# 780-00012-P3_rev4_Sch_M2_Focus_Drive.net
KiCad netlist of a schematic drawn in Altium Designer
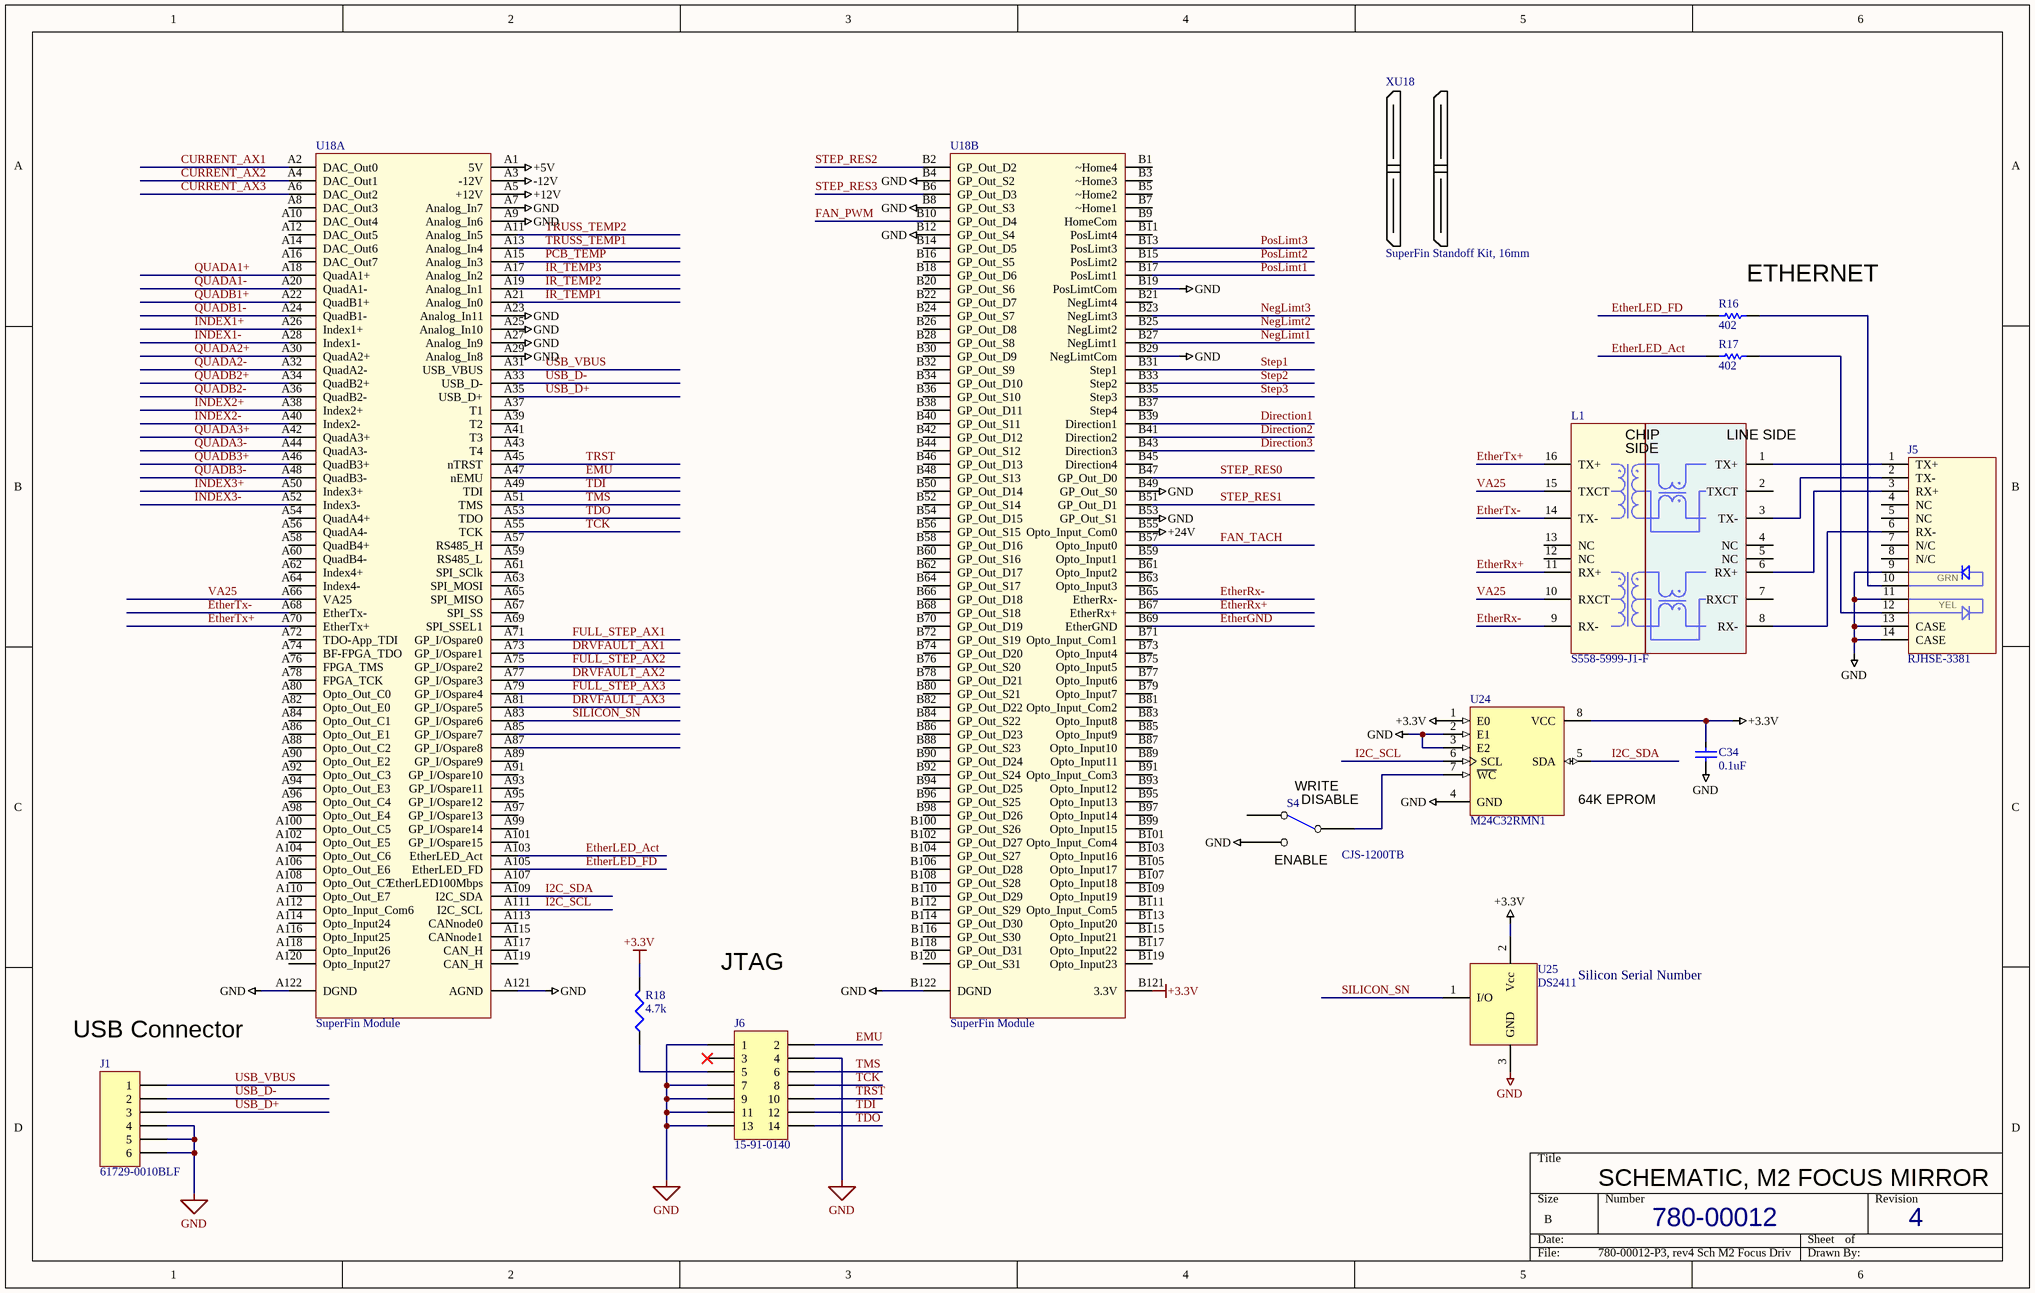
[diagram p0: 780-00012-P3, rev4 Sch M2 Focus Drive.SchDoc]

(export (version "E")
  (design (tool "Eeschema 10.0.6"))
  (components
    (comp (ref "C34")
      (value "0.1uF")
      (footprint "SMD_0805")
      (description "Capacitor")
      (fields (field (name "MANUFACTURER") "AVX") (field (name "Comment") "Cap SMD"))
      (libsource (lib "Richs Schematic Components") (part "Cap SMD"))
    )
    (comp (ref "J1")
      (value "61729-0010BLF")
      (footprint "USB Vertical PCB")
      (description "Header, 6-Pin")
      (fields (field (name "MANUFACTURER") "FCI"))
      (libsource (lib "Miscellaneous Connectors") (part "Header 6"))
    )
    (comp (ref "J5")
      (value "RJHSE-3381")
      (footprint "RJ45, VERT MOUNT, NO MAGNETICS")
      (description "Vertical PC mount, w/o magnetics")
      (libsource (lib "Richs Schematic Components") (part "CONN RJ-45 w/o magnetics"))
    )
    (comp (ref "J6")
      (value "15-91-0140")
      (footprint "HDR2X7")
      (description "Header, 7-Pin, Dual row")
      (fields (field (name "MANUFACTURER") "Molex/Waldom"))
      (libsource (lib "Miscellaneous Connectors") (part "Header 7X2"))
    )
    (comp (ref "L1")
      (value "S558-5999-J1-F")
      (footprint "10/100BT Magetics module")
      (description "10/100BT Magnetics Module")
      (libsource (lib "Richs Schematic Components") (part "Ethernet Magnetics module"))
    )
    (comp (ref "R16")
      (value "402")
      (footprint "SMD_0805")
      (description "Resistor 0805")
      (fields (field (name "MANUFACTURER") "Vishay/Dale") (field (name "Comment") "Res 0805"))
      (libsource (lib "Richs Schematic Components") (part "Res SMD"))
    )
    (comp (ref "R17")
      (value "402")
      (footprint "SMD_0805")
      (description "Resistor 0805")
      (fields (field (name "MANUFACTURER") "Vishay/Dale") (field (name "Comment") "Res 0805"))
      (libsource (lib "Richs Schematic Components") (part "Res SMD"))
    )
    (comp (ref "R18")
      (value "4.7k")
      (footprint "2012[0805]")
      (description "Resistor")
      (fields (field (name "MANUFACTURER") "Dale/Vishay"))
      (libsource (lib "Miscellaneous Devices") (part "Res3"))
    )
    (comp (ref "S4")
      (value "CJS-1200TB")
      (footprint "CAS-120B")
      (fields (field (name "MANUFACTURER") "Copal Electronics"))
      (libsource (lib "JON_1_Library") (part "SW_SPDT_DOUG"))
    )
    (comp (ref "U18")
      (value "SuperFin Module")
      (footprint "SuperFin Footprint")
      (libsource (lib "Richs Schematic Components") (part "SuperFin Module"))
    )
    (comp (ref "U24")
      (value "M24C32RMN1")
      (footprint "SOP8_N")
      (description "32 Kbit Serial I²C Bus EEPROM")
      (libsource (lib "ST Memory EEPROM Serial") (part "M24C32RMN1"))
    )
    (comp (ref "U25")
      (value "DS2411")
      (footprint "SMD_SOT23_3")
      (description "Silicon Serial Number")
      (fields (field (name "MANUFACTURER") "MAXIM"))
      (libsource (lib "Richs Schematic Components") (part "DS2411"))
    )
    (comp (ref "XU18")
      (value "SuperFin Standoff Kit, 16mm")
      (libsource (lib "Richs Schematic Components") (part "SuperFin Standoff Kit, 16mm"))
    )
  )
  (nets
    (net (code "1") (name "+3.3V") (class "Default")
      (node (ref "C34") (pin "2") (pinfunction "2_2") (pintype "passive"))
      (node (ref "R18") (pin "2") (pinfunction "2_2") (pintype "passive"))
      (node (ref "U18") (pin "B121") (pinfunction "3.3V_B121") (pintype "passive"))
      (node (ref "U24") (pin "1") (pinfunction "E0_1") (pintype "input"))
      (node (ref "U24") (pin "8") (pinfunction "VCC_8") (pintype "power_in"))
      (node (ref "U25") (pin "2") (pinfunction "Vcc_2") (pintype "passive"))
    )
    (net (code "2") (name "+5V") (class "Default")
      (node (ref "U18") (pin "A1") (pinfunction "5V_A1") (pintype "passive"))
    )
    (net (code "3") (name "+12V") (class "Default")
      (node (ref "U18") (pin "A5") (pinfunction "+12V_A5") (pintype "passive"))
    )
    (net (code "4") (name "+24V") (class "Default")
      (node (ref "U18") (pin "B55") (pinfunction "Opto_Input_Com0_B55") (pintype "passive"))
    )
    (net (code "5") (name "-12V") (class "Default")
      (node (ref "U18") (pin "A3") (pinfunction "-12V_A3") (pintype "passive"))
    )
    (net (code "6") (name "/CURRENT_AX1") (class "Default")
      (node (ref "U18") (pin "A2") (pinfunction "DAC_Out0_A2") (pintype "passive"))
    )
    (net (code "7") (name "/CURRENT_AX2") (class "Default")
      (node (ref "U18") (pin "A4") (pinfunction "DAC_Out1_A4") (pintype "passive"))
    )
    (net (code "8") (name "/CURRENT_AX3") (class "Default")
      (node (ref "U18") (pin "A6") (pinfunction "DAC_Out2_A6") (pintype "passive"))
    )
    (net (code "9") (name "/DRVFAULT_AX1") (class "Default")
      (node (ref "U18") (pin "A73") (pinfunction "GP_I/Ospare1_A73") (pintype "passive"))
    )
    (net (code "10") (name "/DRVFAULT_AX2") (class "Default")
      (node (ref "U18") (pin "A77") (pinfunction "GP_I/Ospare3_A77") (pintype "passive"))
    )
    (net (code "11") (name "/DRVFAULT_AX3") (class "Default")
      (node (ref "U18") (pin "A81") (pinfunction "GP_I/Ospare5_A81") (pintype "passive"))
    )
    (net (code "12") (name "/Direction1") (class "Default")
      (node (ref "U18") (pin "B39") (pinfunction "Direction1_B39") (pintype "passive"))
    )
    (net (code "13") (name "/Direction2") (class "Default")
      (node (ref "U18") (pin "B41") (pinfunction "Direction2_B41") (pintype "passive"))
    )
    (net (code "14") (name "/Direction3") (class "Default")
      (node (ref "U18") (pin "B43") (pinfunction "Direction3_B43") (pintype "passive"))
    )
    (net (code "15") (name "/EMU") (class "Default")
      (node (ref "J6") (pin "2") (pinfunction "2_2") (pintype "passive"))
      (node (ref "U18") (pin "A47") (pinfunction "nEMU_A47") (pintype "passive"))
    )
    (net (code "16") (name "/EtherGND") (class "Default")
      (node (ref "U18") (pin "B69") (pinfunction "EtherGND_B69") (pintype "passive"))
    )
    (net (code "17") (name "/EtherLED_Act") (class "Default")
      (node (ref "R17") (pin "1") (pinfunction "1_1") (pintype "passive"))
      (node (ref "U18") (pin "A103") (pinfunction "EtherLED_Act_A103") (pintype "passive"))
    )
    (net (code "18") (name "/EtherLED_FD") (class "Default")
      (node (ref "R16") (pin "1") (pinfunction "1_1") (pintype "passive"))
      (node (ref "U18") (pin "A105") (pinfunction "EtherLED_FD_A105") (pintype "passive"))
    )
    (net (code "19") (name "/EtherRx+") (class "Default")
      (node (ref "L1") (pin "11") (pinfunction "RX+_11") (pintype "passive"))
      (node (ref "U18") (pin "B67") (pinfunction "EtherRx+_B67") (pintype "passive"))
    )
    (net (code "20") (name "/EtherRx-") (class "Default")
      (node (ref "L1") (pin "9") (pinfunction "RX-_9") (pintype "passive"))
      (node (ref "U18") (pin "B65") (pinfunction "EtherRx-_B65") (pintype "passive"))
    )
    (net (code "21") (name "/EtherTx+") (class "Default")
      (node (ref "L1") (pin "16") (pinfunction "TX+_16") (pintype "passive"))
      (node (ref "U18") (pin "A70") (pinfunction "EtherTx+_A70") (pintype "passive"))
    )
    (net (code "22") (name "/EtherTx-") (class "Default")
      (node (ref "L1") (pin "14") (pinfunction "TX-_14") (pintype "passive"))
      (node (ref "U18") (pin "A68") (pinfunction "EtherTx-_A68") (pintype "passive"))
    )
    (net (code "23") (name "/FAN_PWM") (class "Default")
      (node (ref "U18") (pin "B10") (pinfunction "GP_Out_D4_B10") (pintype "passive"))
    )
    (net (code "24") (name "/FAN_TACH") (class "Default")
      (node (ref "U18") (pin "B57") (pinfunction "Opto_Input0_B57") (pintype "passive"))
    )
    (net (code "25") (name "/FULL_STEP_AX1") (class "Default")
      (node (ref "U18") (pin "A71") (pinfunction "GP_I/Ospare0_A71") (pintype "passive"))
    )
    (net (code "26") (name "/FULL_STEP_AX2") (class "Default")
      (node (ref "U18") (pin "A75") (pinfunction "GP_I/Ospare2_A75") (pintype "passive"))
    )
    (net (code "27") (name "/FULL_STEP_AX3") (class "Default")
      (node (ref "U18") (pin "A79") (pinfunction "GP_I/Ospare4_A79") (pintype "passive"))
    )
    (net (code "28") (name "/I2C_SCL") (class "Default")
      (node (ref "U18") (pin "A111") (pinfunction "I2C_SCL_A111") (pintype "passive"))
      (node (ref "U24") (pin "6") (pinfunction "SCL_6") (pintype "input"))
    )
    (net (code "29") (name "/I2C_SDA") (class "Default")
      (node (ref "U18") (pin "A109") (pinfunction "I2C_SDA_A109") (pintype "passive"))
      (node (ref "U24") (pin "5") (pinfunction "SDA_5") (pintype "bidirectional"))
    )
    (net (code "30") (name "/INDEX1+") (class "Default")
      (node (ref "U18") (pin "A26") (pinfunction "Index1+_A26") (pintype "passive"))
    )
    (net (code "31") (name "/INDEX1-") (class "Default")
      (node (ref "U18") (pin "A28") (pinfunction "Index1-_A28") (pintype "passive"))
    )
    (net (code "32") (name "/INDEX2+") (class "Default")
      (node (ref "U18") (pin "A38") (pinfunction "Index2+_A38") (pintype "passive"))
    )
    (net (code "33") (name "/INDEX2-") (class "Default")
      (node (ref "U18") (pin "A40") (pinfunction "Index2-_A40") (pintype "passive"))
    )
    (net (code "34") (name "/INDEX3+") (class "Default")
      (node (ref "U18") (pin "A50") (pinfunction "Index3+_A50") (pintype "passive"))
    )
    (net (code "35") (name "/INDEX3-") (class "Default")
      (node (ref "U18") (pin "A52") (pinfunction "Index3-_A52") (pintype "passive"))
    )
    (net (code "36") (name "/IR_TEMP1") (class "Default")
      (node (ref "U18") (pin "A21") (pinfunction "Analog_In0_A21") (pintype "passive"))
    )
    (net (code "37") (name "/IR_TEMP2") (class "Default")
      (node (ref "U18") (pin "A19") (pinfunction "Analog_In1_A19") (pintype "passive"))
    )
    (net (code "38") (name "/IR_TEMP3") (class "Default")
      (node (ref "U18") (pin "A17") (pinfunction "Analog_In2_A17") (pintype "passive"))
    )
    (net (code "39") (name "/NegLimt1") (class "Default")
      (node (ref "U18") (pin "B27") (pinfunction "NegLimt1_B27") (pintype "passive"))
    )
    (net (code "40") (name "/NegLimt2") (class "Default")
      (node (ref "U18") (pin "B25") (pinfunction "NegLimt2_B25") (pintype "passive"))
    )
    (net (code "41") (name "/NegLimt3") (class "Default")
      (node (ref "U18") (pin "B23") (pinfunction "NegLimt3_B23") (pintype "passive"))
    )
    (net (code "42") (name "/PCB_TEMP") (class "Default")
      (node (ref "U18") (pin "A15") (pinfunction "Analog_In3_A15") (pintype "passive"))
    )
    (net (code "43") (name "/PosLimt1") (class "Default")
      (node (ref "U18") (pin "B17") (pinfunction "PosLimt1_B17") (pintype "passive"))
    )
    (net (code "44") (name "/PosLimt2") (class "Default")
      (node (ref "U18") (pin "B15") (pinfunction "PosLimt2_B15") (pintype "passive"))
    )
    (net (code "45") (name "/PosLimt3") (class "Default")
      (node (ref "U18") (pin "B13") (pinfunction "PosLimt3_B13") (pintype "passive"))
    )
    (net (code "46") (name "/QUADA1+") (class "Default")
      (node (ref "U18") (pin "A18") (pinfunction "QuadA1+_A18") (pintype "passive"))
    )
    (net (code "47") (name "/QUADA1-") (class "Default")
      (node (ref "U18") (pin "A20") (pinfunction "QuadA1-_A20") (pintype "passive"))
    )
    (net (code "48") (name "/QUADA2+") (class "Default")
      (node (ref "U18") (pin "A30") (pinfunction "QuadA2+_A30") (pintype "passive"))
    )
    (net (code "49") (name "/QUADA2-") (class "Default")
      (node (ref "U18") (pin "A32") (pinfunction "QuadA2-_A32") (pintype "passive"))
    )
    (net (code "50") (name "/QUADA3+") (class "Default")
      (node (ref "U18") (pin "A42") (pinfunction "QuadA3+_A42") (pintype "passive"))
    )
    (net (code "51") (name "/QUADA3-") (class "Default")
      (node (ref "U18") (pin "A44") (pinfunction "QuadA3-_A44") (pintype "passive"))
    )
    (net (code "52") (name "/QUADB1+") (class "Default")
      (node (ref "U18") (pin "A22") (pinfunction "QuadB1+_A22") (pintype "passive"))
    )
    (net (code "53") (name "/QUADB1-") (class "Default")
      (node (ref "U18") (pin "A24") (pinfunction "QuadB1-_A24") (pintype "passive"))
    )
    (net (code "54") (name "/QUADB2+") (class "Default")
      (node (ref "U18") (pin "A34") (pinfunction "QuadB2+_A34") (pintype "passive"))
    )
    (net (code "55") (name "/QUADB2-") (class "Default")
      (node (ref "U18") (pin "A36") (pinfunction "QuadB2-_A36") (pintype "passive"))
    )
    (net (code "56") (name "/QUADB3+") (class "Default")
      (node (ref "U18") (pin "A46") (pinfunction "QuadB3+_A46") (pintype "passive"))
    )
    (net (code "57") (name "/QUADB3-") (class "Default")
      (node (ref "U18") (pin "A48") (pinfunction "QuadB3-_A48") (pintype "passive"))
    )
    (net (code "58") (name "/SILICON_SN") (class "Default")
      (node (ref "U18") (pin "A83") (pinfunction "GP_I/Ospare6_A83") (pintype "passive"))
      (node (ref "U25") (pin "1") (pinfunction "I/O_1") (pintype "passive"))
    )
    (net (code "59") (name "/STEP_RES0") (class "Default")
      (node (ref "U18") (pin "B47") (pinfunction "GP_Out_D0_B47") (pintype "passive"))
    )
    (net (code "60") (name "/STEP_RES1") (class "Default")
      (node (ref "U18") (pin "B51") (pinfunction "GP_Out_D1_B51") (pintype "passive"))
    )
    (net (code "61") (name "/STEP_RES2") (class "Default")
      (node (ref "U18") (pin "B2") (pinfunction "GP_Out_D2_B2") (pintype "passive"))
    )
    (net (code "62") (name "/STEP_RES3") (class "Default")
      (node (ref "U18") (pin "B6") (pinfunction "GP_Out_D3_B6") (pintype "passive"))
    )
    (net (code "63") (name "/Step1") (class "Default")
      (node (ref "U18") (pin "B31") (pinfunction "Step1_B31") (pintype "passive"))
    )
    (net (code "64") (name "/Step2") (class "Default")
      (node (ref "U18") (pin "B33") (pinfunction "Step2_B33") (pintype "passive"))
    )
    (net (code "65") (name "/Step3") (class "Default")
      (node (ref "U18") (pin "B35") (pinfunction "Step3_B35") (pintype "passive"))
    )
    (net (code "66") (name "/TCK") (class "Default")
      (node (ref "J6") (pin "8") (pinfunction "8_8") (pintype "passive"))
      (node (ref "U18") (pin "A55") (pinfunction "TCK_A55") (pintype "passive"))
    )
    (net (code "67") (name "/TDI") (class "Default")
      (node (ref "J6") (pin "12") (pinfunction "12_12") (pintype "passive"))
      (node (ref "U18") (pin "A49") (pinfunction "TDI_A49") (pintype "passive"))
    )
    (net (code "68") (name "/TDO") (class "Default")
      (node (ref "J6") (pin "14") (pinfunction "14_14") (pintype "passive"))
      (node (ref "U18") (pin "A53") (pinfunction "TDO_A53") (pintype "passive"))
    )
    (net (code "69") (name "/TMS") (class "Default")
      (node (ref "J6") (pin "6") (pinfunction "6_6") (pintype "passive"))
      (node (ref "U18") (pin "A51") (pinfunction "TMS_A51") (pintype "passive"))
    )
    (net (code "70") (name "/TRST") (class "Default")
      (node (ref "J6") (pin "10") (pinfunction "10_10") (pintype "passive"))
      (node (ref "U18") (pin "A45") (pinfunction "nTRST_A45") (pintype "passive"))
    )
    (net (code "71") (name "/TRUSS_TEMP1") (class "Default")
      (node (ref "U18") (pin "A13") (pinfunction "Analog_In4_A13") (pintype "passive"))
    )
    (net (code "72") (name "/TRUSS_TEMP2") (class "Default")
      (node (ref "U18") (pin "A11") (pinfunction "Analog_In5_A11") (pintype "passive"))
    )
    (net (code "73") (name "/USB_D+") (class "Default")
      (node (ref "J1") (pin "3") (pinfunction "3_3") (pintype "passive"))
      (node (ref "U18") (pin "A35") (pinfunction "USB_D+_A35") (pintype "passive"))
    )
    (net (code "74") (name "/USB_D-") (class "Default")
      (node (ref "J1") (pin "2") (pinfunction "2_2") (pintype "passive"))
      (node (ref "U18") (pin "A33") (pinfunction "USB_D-_A33") (pintype "passive"))
    )
    (net (code "75") (name "/USB_VBUS") (class "Default")
      (node (ref "J1") (pin "1") (pinfunction "1_1") (pintype "passive"))
      (node (ref "U18") (pin "A31") (pinfunction "USB_VBUS_A31") (pintype "passive"))
    )
    (net (code "76") (name "/VA25") (class "Default")
      (node (ref "L1") (pin "10") (pinfunction "RXCT_10") (pintype "passive"))
      (node (ref "L1") (pin "15") (pinfunction "TXCT_15") (pintype "passive"))
      (node (ref "U18") (pin "A66") (pinfunction "VA25_A66") (pintype "passive"))
    )
    (net (code "77") (name "GND") (class "Default")
      (node (ref "C34") (pin "1") (pinfunction "1_1") (pintype "passive"))
      (node (ref "J1") (pin "4") (pinfunction "4_4") (pintype "passive"))
      (node (ref "J1") (pin "5") (pinfunction "5_5") (pintype "passive"))
      (node (ref "J1") (pin "6") (pinfunction "6_6") (pintype "passive"))
      (node (ref "J5") (pin "11") (pinfunction "YEL-Cathode_11") (pintype "passive"))
      (node (ref "J5") (pin "13") (pinfunction "CASE_13") (pintype "passive"))
      (node (ref "J5") (pin "14") (pinfunction "CASE_14") (pintype "passive"))
      (node (ref "J5") (pin "9") (pinfunction "GRN-Anode_9") (pintype "passive"))
      (node (ref "J6") (pin "1") (pinfunction "1_1") (pintype "passive"))
      (node (ref "J6") (pin "11") (pinfunction "11_11") (pintype "passive"))
      (node (ref "J6") (pin "13") (pinfunction "13_13") (pintype "passive"))
      (node (ref "J6") (pin "4") (pinfunction "4_4") (pintype "passive"))
      (node (ref "J6") (pin "7") (pinfunction "7_7") (pintype "passive"))
      (node (ref "J6") (pin "9") (pinfunction "9_9") (pintype "passive"))
      (node (ref "S4") (pin "1") (pinfunction "NO_1") (pintype "passive"))
      (node (ref "U18") (pin "A121") (pinfunction "AGND_A121") (pintype "passive"))
      (node (ref "U18") (pin "A122") (pinfunction "DGND_A122") (pintype "passive"))
      (node (ref "U18") (pin "A23") (pinfunction "Analog_In11_A23") (pintype "passive"))
      (node (ref "U18") (pin "A25") (pinfunction "Analog_In10_A25") (pintype "passive"))
      (node (ref "U18") (pin "A27") (pinfunction "Analog_In9_A27") (pintype "passive"))
      (node (ref "U18") (pin "A29") (pinfunction "Analog_In8_A29") (pintype "passive"))
      (node (ref "U18") (pin "A7") (pinfunction "Analog_In7_A7") (pintype "passive"))
      (node (ref "U18") (pin "A9") (pinfunction "Analog_In6_A9") (pintype "passive"))
      (node (ref "U18") (pin "B12") (pinfunction "GP_Out_S4_B12") (pintype "passive"))
      (node (ref "U18") (pin "B122") (pinfunction "DGND_B122") (pintype "passive"))
      (node (ref "U18") (pin "B19") (pinfunction "PosLimtCom_B19") (pintype "passive"))
      (node (ref "U18") (pin "B29") (pinfunction "NegLimtCom_B29") (pintype "passive"))
      (node (ref "U18") (pin "B4") (pinfunction "GP_Out_S2_B4") (pintype "passive"))
      (node (ref "U18") (pin "B49") (pinfunction "GP_Out_S0_B49") (pintype "passive"))
      (node (ref "U18") (pin "B53") (pinfunction "GP_Out_S1_B53") (pintype "passive"))
      (node (ref "U18") (pin "B8") (pinfunction "GP_Out_S3_B8") (pintype "passive"))
      (node (ref "U24") (pin "2") (pinfunction "E1_2") (pintype "input"))
      (node (ref "U24") (pin "3") (pinfunction "E2_3") (pintype "input"))
      (node (ref "U24") (pin "4") (pinfunction "GND_4") (pintype "power_in"))
      (node (ref "U25") (pin "3") (pinfunction "GND_3") (pintype "passive"))
    )
    (net (code "78") (name "Net-(J5-GRN-Cathode)") (class "Default")
      (node (ref "J5") (pin "10") (pinfunction "GRN-Cathode_10") (pintype "passive"))
      (node (ref "R16") (pin "2") (pinfunction "2_2") (pintype "passive"))
    )
    (net (code "79") (name "Net-(J5-RX+)") (class "Default")
      (node (ref "J5") (pin "3") (pinfunction "RX+_3") (pintype "passive"))
      (node (ref "L1") (pin "6") (pinfunction "RX+_6") (pintype "passive"))
    )
    (net (code "80") (name "Net-(J5-RX-)") (class "Default")
      (node (ref "J5") (pin "6") (pinfunction "RX-_6") (pintype "passive"))
      (node (ref "L1") (pin "8") (pinfunction "RX-_8") (pintype "passive"))
    )
    (net (code "81") (name "Net-(J5-TX+)") (class "Default")
      (node (ref "J5") (pin "1") (pinfunction "TX+_1") (pintype "passive"))
      (node (ref "L1") (pin "1") (pinfunction "TX+_1") (pintype "passive"))
    )
    (net (code "82") (name "Net-(J5-TX-)") (class "Default")
      (node (ref "J5") (pin "2") (pinfunction "TX-_2") (pintype "passive"))
      (node (ref "L1") (pin "3") (pinfunction "TX-_3") (pintype "passive"))
    )
    (net (code "83") (name "Net-(J5-YEL-Anode)") (class "Default")
      (node (ref "J5") (pin "12") (pinfunction "YEL-Anode_12") (pintype "passive"))
      (node (ref "R17") (pin "2") (pinfunction "2_2") (pintype "passive"))
    )
    (net (code "84") (name "Net-(J6-Pad5)") (class "Default")
      (node (ref "J6") (pin "5") (pinfunction "5_5") (pintype "passive"))
      (node (ref "R18") (pin "1") (pinfunction "1_1") (pintype "passive"))
    )
    (net (code "85") (name "Net-(S4-COM)") (class "Default")
      (node (ref "S4") (pin "2") (pinfunction "COM_2") (pintype "passive"))
      (node (ref "U24") (pin "7") (pinfunction "~{WC}_7") (pintype "input"))
    )
    (net (code "86") (name "unconnected-(J5-NC-Pad4)") (class "Default")
      (node (ref "J5") (pin "4") (pinfunction "NC_4") (pintype "passive"))
    )
    (net (code "87") (name "unconnected-(J5-NC-Pad5)") (class "Default")
      (node (ref "J5") (pin "5") (pinfunction "NC_5") (pintype "passive"))
    )
    (net (code "88") (name "unconnected-(J5-N{slash}C-Pad7)") (class "Default")
      (node (ref "J5") (pin "7") (pinfunction "N/C_7") (pintype "passive"))
    )
    (net (code "89") (name "unconnected-(J5-N{slash}C-Pad8)") (class "Default")
      (node (ref "J5") (pin "8") (pinfunction "N/C_8") (pintype "passive"))
    )
    (net (code "90") (name "unconnected-(J6-Pad3)") (class "Default")
      (node (ref "J6") (pin "3") (pinfunction "3_3") (pintype "passive+no_connect"))
    )
    (net (code "91") (name "unconnected-(L1-NC-Pad4)") (class "Default")
      (node (ref "L1") (pin "4") (pinfunction "NC_4") (pintype "passive"))
    )
    (net (code "92") (name "unconnected-(L1-NC-Pad5)") (class "Default")
      (node (ref "L1") (pin "5") (pinfunction "NC_5") (pintype "passive"))
    )
    (net (code "93") (name "unconnected-(L1-NC-Pad12)") (class "Default")
      (node (ref "L1") (pin "12") (pinfunction "NC_12") (pintype "passive"))
    )
    (net (code "94") (name "unconnected-(L1-NC-Pad13)") (class "Default")
      (node (ref "L1") (pin "13") (pinfunction "NC_13") (pintype "passive"))
    )
    (net (code "95") (name "unconnected-(L1-RXCT-Pad7)") (class "Default")
      (node (ref "L1") (pin "7") (pinfunction "RXCT_7") (pintype "passive"))
    )
    (net (code "96") (name "unconnected-(L1-TXCT-Pad2)") (class "Default")
      (node (ref "L1") (pin "2") (pinfunction "TXCT_2") (pintype "passive"))
    )
    (net (code "97") (name "unconnected-(S4-NC-Pad3)") (class "Default")
      (node (ref "S4") (pin "3") (pinfunction "NC_3") (pintype "passive"))
    )
    (net (code "98") (name "unconnected-(U18A-BF-FPGA_TDO-PadA74)") (class "Default")
      (node (ref "U18") (pin "A74") (pinfunction "BF-FPGA_TDO_A74") (pintype "passive"))
    )
    (net (code "99") (name "unconnected-(U18A-CAN_H-PadA117)") (class "Default")
      (node (ref "U18") (pin "A117") (pinfunction "CAN_H_A117") (pintype "passive"))
    )
    (net (code "100") (name "unconnected-(U18A-CAN_H-PadA119)") (class "Default")
      (node (ref "U18") (pin "A119") (pinfunction "CAN_H_A119") (pintype "passive"))
    )
    (net (code "101") (name "unconnected-(U18A-CANnode0-PadA113)") (class "Default")
      (node (ref "U18") (pin "A113") (pinfunction "CANnode0_A113") (pintype "passive"))
    )
    (net (code "102") (name "unconnected-(U18A-CANnode1-PadA115)") (class "Default")
      (node (ref "U18") (pin "A115") (pinfunction "CANnode1_A115") (pintype "passive"))
    )
    (net (code "103") (name "unconnected-(U18A-DAC_Out3-PadA8)") (class "Default")
      (node (ref "U18") (pin "A8") (pinfunction "DAC_Out3_A8") (pintype "passive"))
    )
    (net (code "104") (name "unconnected-(U18A-DAC_Out4-PadA10)") (class "Default")
      (node (ref "U18") (pin "A10") (pinfunction "DAC_Out4_A10") (pintype "passive"))
    )
    (net (code "105") (name "unconnected-(U18A-DAC_Out5-PadA12)") (class "Default")
      (node (ref "U18") (pin "A12") (pinfunction "DAC_Out5_A12") (pintype "passive"))
    )
    (net (code "106") (name "unconnected-(U18A-DAC_Out6-PadA14)") (class "Default")
      (node (ref "U18") (pin "A14") (pinfunction "DAC_Out6_A14") (pintype "passive"))
    )
    (net (code "107") (name "unconnected-(U18A-DAC_Out7-PadA16)") (class "Default")
      (node (ref "U18") (pin "A16") (pinfunction "DAC_Out7_A16") (pintype "passive"))
    )
    (net (code "108") (name "unconnected-(U18A-EtherLED100Mbps-PadA107)") (class "Default")
      (node (ref "U18") (pin "A107") (pinfunction "EtherLED100Mbps_A107") (pintype "passive"))
    )
    (net (code "109") (name "unconnected-(U18A-FPGA_TCK-PadA78)") (class "Default")
      (node (ref "U18") (pin "A78") (pinfunction "FPGA_TCK_A78") (pintype "passive"))
    )
    (net (code "110") (name "unconnected-(U18A-FPGA_TMS-PadA76)") (class "Default")
      (node (ref "U18") (pin "A76") (pinfunction "FPGA_TMS_A76") (pintype "passive"))
    )
    (net (code "111") (name "unconnected-(U18A-GP_I{slash}Ospare7-PadA85)") (class "Default")
      (node (ref "U18") (pin "A85") (pinfunction "GP_I/Ospare7_A85") (pintype "passive"))
    )
    (net (code "112") (name "unconnected-(U18A-GP_I{slash}Ospare8-PadA87)") (class "Default")
      (node (ref "U18") (pin "A87") (pinfunction "GP_I/Ospare8_A87") (pintype "passive"))
    )
    (net (code "113") (name "unconnected-(U18A-GP_I{slash}Ospare9-PadA89)") (class "Default")
      (node (ref "U18") (pin "A89") (pinfunction "GP_I/Ospare9_A89") (pintype "passive"))
    )
    (net (code "114") (name "unconnected-(U18A-GP_I{slash}Ospare10-PadA91)") (class "Default")
      (node (ref "U18") (pin "A91") (pinfunction "GP_I/Ospare10_A91") (pintype "passive"))
    )
    (net (code "115") (name "unconnected-(U18A-GP_I{slash}Ospare11-PadA93)") (class "Default")
      (node (ref "U18") (pin "A93") (pinfunction "GP_I/Ospare11_A93") (pintype "passive"))
    )
    (net (code "116") (name "unconnected-(U18A-GP_I{slash}Ospare12-PadA95)") (class "Default")
      (node (ref "U18") (pin "A95") (pinfunction "GP_I/Ospare12_A95") (pintype "passive"))
    )
    (net (code "117") (name "unconnected-(U18A-GP_I{slash}Ospare13-PadA97)") (class "Default")
      (node (ref "U18") (pin "A97") (pinfunction "GP_I/Ospare13_A97") (pintype "passive"))
    )
    (net (code "118") (name "unconnected-(U18A-GP_I{slash}Ospare14-PadA99)") (class "Default")
      (node (ref "U18") (pin "A99") (pinfunction "GP_I/Ospare14_A99") (pintype "passive"))
    )
    (net (code "119") (name "unconnected-(U18A-GP_I{slash}Ospare15-PadA101)") (class "Default")
      (node (ref "U18") (pin "A101") (pinfunction "GP_I/Ospare15_A101") (pintype "passive"))
    )
    (net (code "120") (name "unconnected-(U18A-Index4+-PadA62)") (class "Default")
      (node (ref "U18") (pin "A62") (pinfunction "Index4+_A62") (pintype "passive"))
    )
    (net (code "121") (name "unconnected-(U18A-Index4--PadA64)") (class "Default")
      (node (ref "U18") (pin "A64") (pinfunction "Index4-_A64") (pintype "passive"))
    )
    (net (code "122") (name "unconnected-(U18A-Opto_Input24-PadA114)") (class "Default")
      (node (ref "U18") (pin "A114") (pinfunction "Opto_Input24_A114") (pintype "passive"))
    )
    (net (code "123") (name "unconnected-(U18A-Opto_Input25-PadA116)") (class "Default")
      (node (ref "U18") (pin "A116") (pinfunction "Opto_Input25_A116") (pintype "passive"))
    )
    (net (code "124") (name "unconnected-(U18A-Opto_Input26-PadA118)") (class "Default")
      (node (ref "U18") (pin "A118") (pinfunction "Opto_Input26_A118") (pintype "passive"))
    )
    (net (code "125") (name "unconnected-(U18A-Opto_Input27-PadA120)") (class "Default")
      (node (ref "U18") (pin "A120") (pinfunction "Opto_Input27_A120") (pintype "passive"))
    )
    (net (code "126") (name "unconnected-(U18A-Opto_Input_Com6-PadA112)") (class "Default")
      (node (ref "U18") (pin "A112") (pinfunction "Opto_Input_Com6_A112") (pintype "passive"))
    )
    (net (code "127") (name "unconnected-(U18A-Opto_Out_C0-PadA80)") (class "Default")
      (node (ref "U18") (pin "A80") (pinfunction "Opto_Out_C0_A80") (pintype "passive"))
    )
    (net (code "128") (name "unconnected-(U18A-Opto_Out_C1-PadA84)") (class "Default")
      (node (ref "U18") (pin "A84") (pinfunction "Opto_Out_C1_A84") (pintype "passive"))
    )
    (net (code "129") (name "unconnected-(U18A-Opto_Out_C2-PadA88)") (class "Default")
      (node (ref "U18") (pin "A88") (pinfunction "Opto_Out_C2_A88") (pintype "passive"))
    )
    (net (code "130") (name "unconnected-(U18A-Opto_Out_C3-PadA92)") (class "Default")
      (node (ref "U18") (pin "A92") (pinfunction "Opto_Out_C3_A92") (pintype "passive"))
    )
    (net (code "131") (name "unconnected-(U18A-Opto_Out_C4-PadA96)") (class "Default")
      (node (ref "U18") (pin "A96") (pinfunction "Opto_Out_C4_A96") (pintype "passive"))
    )
    (net (code "132") (name "unconnected-(U18A-Opto_Out_C5-PadA100)") (class "Default")
      (node (ref "U18") (pin "A100") (pinfunction "Opto_Out_C5_A100") (pintype "passive"))
    )
    (net (code "133") (name "unconnected-(U18A-Opto_Out_C6-PadA104)") (class "Default")
      (node (ref "U18") (pin "A104") (pinfunction "Opto_Out_C6_A104") (pintype "passive"))
    )
    (net (code "134") (name "unconnected-(U18A-Opto_Out_C7-PadA108)") (class "Default")
      (node (ref "U18") (pin "A108") (pinfunction "Opto_Out_C7_A108") (pintype "passive"))
    )
    (net (code "135") (name "unconnected-(U18A-Opto_Out_E0-PadA82)") (class "Default")
      (node (ref "U18") (pin "A82") (pinfunction "Opto_Out_E0_A82") (pintype "passive"))
    )
    (net (code "136") (name "unconnected-(U18A-Opto_Out_E1-PadA86)") (class "Default")
      (node (ref "U18") (pin "A86") (pinfunction "Opto_Out_E1_A86") (pintype "passive"))
    )
    (net (code "137") (name "unconnected-(U18A-Opto_Out_E2-PadA90)") (class "Default")
      (node (ref "U18") (pin "A90") (pinfunction "Opto_Out_E2_A90") (pintype "passive"))
    )
    (net (code "138") (name "unconnected-(U18A-Opto_Out_E3-PadA94)") (class "Default")
      (node (ref "U18") (pin "A94") (pinfunction "Opto_Out_E3_A94") (pintype "passive"))
    )
    (net (code "139") (name "unconnected-(U18A-Opto_Out_E4-PadA98)") (class "Default")
      (node (ref "U18") (pin "A98") (pinfunction "Opto_Out_E4_A98") (pintype "passive"))
    )
    (net (code "140") (name "unconnected-(U18A-Opto_Out_E5-PadA102)") (class "Default")
      (node (ref "U18") (pin "A102") (pinfunction "Opto_Out_E5_A102") (pintype "passive"))
    )
    (net (code "141") (name "unconnected-(U18A-Opto_Out_E6-PadA106)") (class "Default")
      (node (ref "U18") (pin "A106") (pinfunction "Opto_Out_E6_A106") (pintype "passive"))
    )
    (net (code "142") (name "unconnected-(U18A-Opto_Out_E7-PadA110)") (class "Default")
      (node (ref "U18") (pin "A110") (pinfunction "Opto_Out_E7_A110") (pintype "passive"))
    )
    (net (code "143") (name "unconnected-(U18A-QuadA4+-PadA54)") (class "Default")
      (node (ref "U18") (pin "A54") (pinfunction "QuadA4+_A54") (pintype "passive"))
    )
    (net (code "144") (name "unconnected-(U18A-QuadA4--PadA56)") (class "Default")
      (node (ref "U18") (pin "A56") (pinfunction "QuadA4-_A56") (pintype "passive"))
    )
    (net (code "145") (name "unconnected-(U18A-QuadB4+-PadA58)") (class "Default")
      (node (ref "U18") (pin "A58") (pinfunction "QuadB4+_A58") (pintype "passive"))
    )
    (net (code "146") (name "unconnected-(U18A-QuadB4--PadA60)") (class "Default")
      (node (ref "U18") (pin "A60") (pinfunction "QuadB4-_A60") (pintype "passive"))
    )
    (net (code "147") (name "unconnected-(U18A-RS485_H-PadA57)") (class "Default")
      (node (ref "U18") (pin "A57") (pinfunction "RS485_H_A57") (pintype "passive"))
    )
    (net (code "148") (name "unconnected-(U18A-RS485_L-PadA59)") (class "Default")
      (node (ref "U18") (pin "A59") (pinfunction "RS485_L_A59") (pintype "passive"))
    )
    (net (code "149") (name "unconnected-(U18A-SPI_MISO-PadA65)") (class "Default")
      (node (ref "U18") (pin "A65") (pinfunction "SPI_MISO_A65") (pintype "passive"))
    )
    (net (code "150") (name "unconnected-(U18A-SPI_MOSI-PadA63)") (class "Default")
      (node (ref "U18") (pin "A63") (pinfunction "SPI_MOSI_A63") (pintype "passive"))
    )
    (net (code "151") (name "unconnected-(U18A-SPI_SClk-PadA61)") (class "Default")
      (node (ref "U18") (pin "A61") (pinfunction "SPI_SClk_A61") (pintype "passive"))
    )
    (net (code "152") (name "unconnected-(U18A-SPI_SS-PadA67)") (class "Default")
      (node (ref "U18") (pin "A67") (pinfunction "SPI_SS_A67") (pintype "passive"))
    )
    (net (code "153") (name "unconnected-(U18A-SPI_SSEL1-PadA69)") (class "Default")
      (node (ref "U18") (pin "A69") (pinfunction "SPI_SSEL1_A69") (pintype "passive"))
    )
    (net (code "154") (name "unconnected-(U18A-T1-PadA37)") (class "Default")
      (node (ref "U18") (pin "A37") (pinfunction "T1_A37") (pintype "passive"))
    )
    (net (code "155") (name "unconnected-(U18A-T2-PadA39)") (class "Default")
      (node (ref "U18") (pin "A39") (pinfunction "T2_A39") (pintype "passive"))
    )
    (net (code "156") (name "unconnected-(U18A-T3-PadA41)") (class "Default")
      (node (ref "U18") (pin "A41") (pinfunction "T3_A41") (pintype "passive"))
    )
    (net (code "157") (name "unconnected-(U18A-T4-PadA43)") (class "Default")
      (node (ref "U18") (pin "A43") (pinfunction "T4_A43") (pintype "passive"))
    )
    (net (code "158") (name "unconnected-(U18A-TDO-App_TDI-PadA72)") (class "Default")
      (node (ref "U18") (pin "A72") (pinfunction "TDO-App_TDI_A72") (pintype "passive"))
    )
    (net (code "159") (name "unconnected-(U18B-Direction4-PadB45)") (class "Default")
      (node (ref "U18") (pin "B45") (pinfunction "Direction4_B45") (pintype "passive"))
    )
    (net (code "160") (name "unconnected-(U18B-GP_Out_D5-PadB14)") (class "Default")
      (node (ref "U18") (pin "B14") (pinfunction "GP_Out_D5_B14") (pintype "passive"))
    )
    (net (code "161") (name "unconnected-(U18B-GP_Out_D6-PadB18)") (class "Default")
      (node (ref "U18") (pin "B18") (pinfunction "GP_Out_D6_B18") (pintype "passive"))
    )
    (net (code "162") (name "unconnected-(U18B-GP_Out_D7-PadB22)") (class "Default")
      (node (ref "U18") (pin "B22") (pinfunction "GP_Out_D7_B22") (pintype "passive"))
    )
    (net (code "163") (name "unconnected-(U18B-GP_Out_D8-PadB26)") (class "Default")
      (node (ref "U18") (pin "B26") (pinfunction "GP_Out_D8_B26") (pintype "passive"))
    )
    (net (code "164") (name "unconnected-(U18B-GP_Out_D9-PadB30)") (class "Default")
      (node (ref "U18") (pin "B30") (pinfunction "GP_Out_D9_B30") (pintype "passive"))
    )
    (net (code "165") (name "unconnected-(U18B-GP_Out_D10-PadB34)") (class "Default")
      (node (ref "U18") (pin "B34") (pinfunction "GP_Out_D10_B34") (pintype "passive"))
    )
    (net (code "166") (name "unconnected-(U18B-GP_Out_D11-PadB38)") (class "Default")
      (node (ref "U18") (pin "B38") (pinfunction "GP_Out_D11_B38") (pintype "passive"))
    )
    (net (code "167") (name "unconnected-(U18B-GP_Out_D12-PadB42)") (class "Default")
      (node (ref "U18") (pin "B42") (pinfunction "GP_Out_D12_B42") (pintype "passive"))
    )
    (net (code "168") (name "unconnected-(U18B-GP_Out_D13-PadB46)") (class "Default")
      (node (ref "U18") (pin "B46") (pinfunction "GP_Out_D13_B46") (pintype "passive"))
    )
    (net (code "169") (name "unconnected-(U18B-GP_Out_D14-PadB50)") (class "Default")
      (node (ref "U18") (pin "B50") (pinfunction "GP_Out_D14_B50") (pintype "passive"))
    )
    (net (code "170") (name "unconnected-(U18B-GP_Out_D15-PadB54)") (class "Default")
      (node (ref "U18") (pin "B54") (pinfunction "GP_Out_D15_B54") (pintype "passive"))
    )
    (net (code "171") (name "unconnected-(U18B-GP_Out_D16-PadB58)") (class "Default")
      (node (ref "U18") (pin "B58") (pinfunction "GP_Out_D16_B58") (pintype "passive"))
    )
    (net (code "172") (name "unconnected-(U18B-GP_Out_D17-PadB62)") (class "Default")
      (node (ref "U18") (pin "B62") (pinfunction "GP_Out_D17_B62") (pintype "passive"))
    )
    (net (code "173") (name "unconnected-(U18B-GP_Out_D18-PadB66)") (class "Default")
      (node (ref "U18") (pin "B66") (pinfunction "GP_Out_D18_B66") (pintype "passive"))
    )
    (net (code "174") (name "unconnected-(U18B-GP_Out_D19-PadB70)") (class "Default")
      (node (ref "U18") (pin "B70") (pinfunction "GP_Out_D19_B70") (pintype "passive"))
    )
    (net (code "175") (name "unconnected-(U18B-GP_Out_D20-PadB74)") (class "Default")
      (node (ref "U18") (pin "B74") (pinfunction "GP_Out_D20_B74") (pintype "passive"))
    )
    (net (code "176") (name "unconnected-(U18B-GP_Out_D21-PadB78)") (class "Default")
      (node (ref "U18") (pin "B78") (pinfunction "GP_Out_D21_B78") (pintype "passive"))
    )
    (net (code "177") (name "unconnected-(U18B-GP_Out_D22-PadB82)") (class "Default")
      (node (ref "U18") (pin "B82") (pinfunction "GP_Out_D22_B82") (pintype "passive"))
    )
    (net (code "178") (name "unconnected-(U18B-GP_Out_D23-PadB86)") (class "Default")
      (node (ref "U18") (pin "B86") (pinfunction "GP_Out_D23_B86") (pintype "passive"))
    )
    (net (code "179") (name "unconnected-(U18B-GP_Out_D24-PadB90)") (class "Default")
      (node (ref "U18") (pin "B90") (pinfunction "GP_Out_D24_B90") (pintype "passive"))
    )
    (net (code "180") (name "unconnected-(U18B-GP_Out_D25-PadB94)") (class "Default")
      (node (ref "U18") (pin "B94") (pinfunction "GP_Out_D25_B94") (pintype "passive"))
    )
    (net (code "181") (name "unconnected-(U18B-GP_Out_D26-PadB98)") (class "Default")
      (node (ref "U18") (pin "B98") (pinfunction "GP_Out_D26_B98") (pintype "passive"))
    )
    (net (code "182") (name "unconnected-(U18B-GP_Out_D27-PadB102)") (class "Default")
      (node (ref "U18") (pin "B102") (pinfunction "GP_Out_D27_B102") (pintype "passive"))
    )
    (net (code "183") (name "unconnected-(U18B-GP_Out_D28-PadB106)") (class "Default")
      (node (ref "U18") (pin "B106") (pinfunction "GP_Out_D28_B106") (pintype "passive"))
    )
    (net (code "184") (name "unconnected-(U18B-GP_Out_D29-PadB110)") (class "Default")
      (node (ref "U18") (pin "B110") (pinfunction "GP_Out_D29_B110") (pintype "passive"))
    )
    (net (code "185") (name "unconnected-(U18B-GP_Out_D30-PadB114)") (class "Default")
      (node (ref "U18") (pin "B114") (pinfunction "GP_Out_D30_B114") (pintype "passive"))
    )
    (net (code "186") (name "unconnected-(U18B-GP_Out_D31-PadB118)") (class "Default")
      (node (ref "U18") (pin "B118") (pinfunction "GP_Out_D31_B118") (pintype "passive"))
    )
    (net (code "187") (name "unconnected-(U18B-GP_Out_S5-PadB16)") (class "Default")
      (node (ref "U18") (pin "B16") (pinfunction "GP_Out_S5_B16") (pintype "passive"))
    )
    (net (code "188") (name "unconnected-(U18B-GP_Out_S6-PadB20)") (class "Default")
      (node (ref "U18") (pin "B20") (pinfunction "GP_Out_S6_B20") (pintype "passive"))
    )
    (net (code "189") (name "unconnected-(U18B-GP_Out_S7-PadB24)") (class "Default")
      (node (ref "U18") (pin "B24") (pinfunction "GP_Out_S7_B24") (pintype "passive"))
    )
    (net (code "190") (name "unconnected-(U18B-GP_Out_S8-PadB28)") (class "Default")
      (node (ref "U18") (pin "B28") (pinfunction "GP_Out_S8_B28") (pintype "passive"))
    )
    (net (code "191") (name "unconnected-(U18B-GP_Out_S9-PadB32)") (class "Default")
      (node (ref "U18") (pin "B32") (pinfunction "GP_Out_S9_B32") (pintype "passive"))
    )
    (net (code "192") (name "unconnected-(U18B-GP_Out_S10-PadB36)") (class "Default")
      (node (ref "U18") (pin "B36") (pinfunction "GP_Out_S10_B36") (pintype "passive"))
    )
    (net (code "193") (name "unconnected-(U18B-GP_Out_S11-PadB40)") (class "Default")
      (node (ref "U18") (pin "B40") (pinfunction "GP_Out_S11_B40") (pintype "passive"))
    )
    (net (code "194") (name "unconnected-(U18B-GP_Out_S12-PadB44)") (class "Default")
      (node (ref "U18") (pin "B44") (pinfunction "GP_Out_S12_B44") (pintype "passive"))
    )
    (net (code "195") (name "unconnected-(U18B-GP_Out_S13-PadB48)") (class "Default")
      (node (ref "U18") (pin "B48") (pinfunction "GP_Out_S13_B48") (pintype "passive"))
    )
    (net (code "196") (name "unconnected-(U18B-GP_Out_S14-PadB52)") (class "Default")
      (node (ref "U18") (pin "B52") (pinfunction "GP_Out_S14_B52") (pintype "passive"))
    )
    (net (code "197") (name "unconnected-(U18B-GP_Out_S15-PadB56)") (class "Default")
      (node (ref "U18") (pin "B56") (pinfunction "GP_Out_S15_B56") (pintype "passive"))
    )
    (net (code "198") (name "unconnected-(U18B-GP_Out_S16-PadB60)") (class "Default")
      (node (ref "U18") (pin "B60") (pinfunction "GP_Out_S16_B60") (pintype "passive"))
    )
    (net (code "199") (name "unconnected-(U18B-GP_Out_S17-PadB64)") (class "Default")
      (node (ref "U18") (pin "B64") (pinfunction "GP_Out_S17_B64") (pintype "passive"))
    )
    (net (code "200") (name "unconnected-(U18B-GP_Out_S18-PadB68)") (class "Default")
      (node (ref "U18") (pin "B68") (pinfunction "GP_Out_S18_B68") (pintype "passive"))
    )
    (net (code "201") (name "unconnected-(U18B-GP_Out_S19-PadB72)") (class "Default")
      (node (ref "U18") (pin "B72") (pinfunction "GP_Out_S19_B72") (pintype "passive"))
    )
    (net (code "202") (name "unconnected-(U18B-GP_Out_S20-PadB76)") (class "Default")
      (node (ref "U18") (pin "B76") (pinfunction "GP_Out_S20_B76") (pintype "passive"))
    )
    (net (code "203") (name "unconnected-(U18B-GP_Out_S21-PadB80)") (class "Default")
      (node (ref "U18") (pin "B80") (pinfunction "GP_Out_S21_B80") (pintype "passive"))
    )
    (net (code "204") (name "unconnected-(U18B-GP_Out_S22-PadB84)") (class "Default")
      (node (ref "U18") (pin "B84") (pinfunction "GP_Out_S22_B84") (pintype "passive"))
    )
    (net (code "205") (name "unconnected-(U18B-GP_Out_S23-PadB88)") (class "Default")
      (node (ref "U18") (pin "B88") (pinfunction "GP_Out_S23_B88") (pintype "passive"))
    )
    (net (code "206") (name "unconnected-(U18B-GP_Out_S24-PadB92)") (class "Default")
      (node (ref "U18") (pin "B92") (pinfunction "GP_Out_S24_B92") (pintype "passive"))
    )
    (net (code "207") (name "unconnected-(U18B-GP_Out_S25-PadB96)") (class "Default")
      (node (ref "U18") (pin "B96") (pinfunction "GP_Out_S25_B96") (pintype "passive"))
    )
    (net (code "208") (name "unconnected-(U18B-GP_Out_S26-PadB100)") (class "Default")
      (node (ref "U18") (pin "B100") (pinfunction "GP_Out_S26_B100") (pintype "passive"))
    )
    (net (code "209") (name "unconnected-(U18B-GP_Out_S27-PadB104)") (class "Default")
      (node (ref "U18") (pin "B104") (pinfunction "GP_Out_S27_B104") (pintype "passive"))
    )
    (net (code "210") (name "unconnected-(U18B-GP_Out_S28-PadB108)") (class "Default")
      (node (ref "U18") (pin "B108") (pinfunction "GP_Out_S28_B108") (pintype "passive"))
    )
    (net (code "211") (name "unconnected-(U18B-GP_Out_S29-PadB112)") (class "Default")
      (node (ref "U18") (pin "B112") (pinfunction "GP_Out_S29_B112") (pintype "passive"))
    )
    (net (code "212") (name "unconnected-(U18B-GP_Out_S30-PadB116)") (class "Default")
      (node (ref "U18") (pin "B116") (pinfunction "GP_Out_S30_B116") (pintype "passive"))
    )
    (net (code "213") (name "unconnected-(U18B-GP_Out_S31-PadB120)") (class "Default")
      (node (ref "U18") (pin "B120") (pinfunction "GP_Out_S31_B120") (pintype "passive"))
    )
    (net (code "214") (name "unconnected-(U18B-HomeCom-PadB9)") (class "Default")
      (node (ref "U18") (pin "B9") (pinfunction "HomeCom_B9") (pintype "passive"))
    )
    (net (code "215") (name "unconnected-(U18B-NegLimt4-PadB21)") (class "Default")
      (node (ref "U18") (pin "B21") (pinfunction "NegLimt4_B21") (pintype "passive"))
    )
    (net (code "216") (name "unconnected-(U18B-Opto_Input1-PadB59)") (class "Default")
      (node (ref "U18") (pin "B59") (pinfunction "Opto_Input1_B59") (pintype "passive"))
    )
    (net (code "217") (name "unconnected-(U18B-Opto_Input2-PadB61)") (class "Default")
      (node (ref "U18") (pin "B61") (pinfunction "Opto_Input2_B61") (pintype "passive"))
    )
    (net (code "218") (name "unconnected-(U18B-Opto_Input3-PadB63)") (class "Default")
      (node (ref "U18") (pin "B63") (pinfunction "Opto_Input3_B63") (pintype "passive"))
    )
    (net (code "219") (name "unconnected-(U18B-Opto_Input4-PadB73)") (class "Default")
      (node (ref "U18") (pin "B73") (pinfunction "Opto_Input4_B73") (pintype "passive"))
    )
    (net (code "220") (name "unconnected-(U18B-Opto_Input5-PadB75)") (class "Default")
      (node (ref "U18") (pin "B75") (pinfunction "Opto_Input5_B75") (pintype "passive"))
    )
    (net (code "221") (name "unconnected-(U18B-Opto_Input6-PadB77)") (class "Default")
      (node (ref "U18") (pin "B77") (pinfunction "Opto_Input6_B77") (pintype "passive"))
    )
    (net (code "222") (name "unconnected-(U18B-Opto_Input7-PadB79)") (class "Default")
      (node (ref "U18") (pin "B79") (pinfunction "Opto_Input7_B79") (pintype "passive"))
    )
    (net (code "223") (name "unconnected-(U18B-Opto_Input8-PadB83)") (class "Default")
      (node (ref "U18") (pin "B83") (pinfunction "Opto_Input8_B83") (pintype "passive"))
    )
    (net (code "224") (name "unconnected-(U18B-Opto_Input9-PadB85)") (class "Default")
      (node (ref "U18") (pin "B85") (pinfunction "Opto_Input9_B85") (pintype "passive"))
    )
    (net (code "225") (name "unconnected-(U18B-Opto_Input10-PadB87)") (class "Default")
      (node (ref "U18") (pin "B87") (pinfunction "Opto_Input10_B87") (pintype "passive"))
    )
    (net (code "226") (name "unconnected-(U18B-Opto_Input11-PadB89)") (class "Default")
      (node (ref "U18") (pin "B89") (pinfunction "Opto_Input11_B89") (pintype "passive"))
    )
    (net (code "227") (name "unconnected-(U18B-Opto_Input12-PadB93)") (class "Default")
      (node (ref "U18") (pin "B93") (pinfunction "Opto_Input12_B93") (pintype "passive"))
    )
    (net (code "228") (name "unconnected-(U18B-Opto_Input13-PadB95)") (class "Default")
      (node (ref "U18") (pin "B95") (pinfunction "Opto_Input13_B95") (pintype "passive"))
    )
    (net (code "229") (name "unconnected-(U18B-Opto_Input14-PadB97)") (class "Default")
      (node (ref "U18") (pin "B97") (pinfunction "Opto_Input14_B97") (pintype "passive"))
    )
    (net (code "230") (name "unconnected-(U18B-Opto_Input15-PadB99)") (class "Default")
      (node (ref "U18") (pin "B99") (pinfunction "Opto_Input15_B99") (pintype "passive"))
    )
    (net (code "231") (name "unconnected-(U18B-Opto_Input16-PadB103)") (class "Default")
      (node (ref "U18") (pin "B103") (pinfunction "Opto_Input16_B103") (pintype "passive"))
    )
    (net (code "232") (name "unconnected-(U18B-Opto_Input17-PadB105)") (class "Default")
      (node (ref "U18") (pin "B105") (pinfunction "Opto_Input17_B105") (pintype "passive"))
    )
    (net (code "233") (name "unconnected-(U18B-Opto_Input18-PadB107)") (class "Default")
      (node (ref "U18") (pin "B107") (pinfunction "Opto_Input18_B107") (pintype "passive"))
    )
    (net (code "234") (name "unconnected-(U18B-Opto_Input19-PadB109)") (class "Default")
      (node (ref "U18") (pin "B109") (pinfunction "Opto_Input19_B109") (pintype "passive"))
    )
    (net (code "235") (name "unconnected-(U18B-Opto_Input20-PadB113)") (class "Default")
      (node (ref "U18") (pin "B113") (pinfunction "Opto_Input20_B113") (pintype "passive"))
    )
    (net (code "236") (name "unconnected-(U18B-Opto_Input21-PadB115)") (class "Default")
      (node (ref "U18") (pin "B115") (pinfunction "Opto_Input21_B115") (pintype "passive"))
    )
    (net (code "237") (name "unconnected-(U18B-Opto_Input22-PadB117)") (class "Default")
      (node (ref "U18") (pin "B117") (pinfunction "Opto_Input22_B117") (pintype "passive"))
    )
    (net (code "238") (name "unconnected-(U18B-Opto_Input23-PadB119)") (class "Default")
      (node (ref "U18") (pin "B119") (pinfunction "Opto_Input23_B119") (pintype "passive"))
    )
    (net (code "239") (name "unconnected-(U18B-Opto_Input_Com1-PadB71)") (class "Default")
      (node (ref "U18") (pin "B71") (pinfunction "Opto_Input_Com1_B71") (pintype "passive"))
    )
    (net (code "240") (name "unconnected-(U18B-Opto_Input_Com2-PadB81)") (class "Default")
      (node (ref "U18") (pin "B81") (pinfunction "Opto_Input_Com2_B81") (pintype "passive"))
    )
    (net (code "241") (name "unconnected-(U18B-Opto_Input_Com3-PadB91)") (class "Default")
      (node (ref "U18") (pin "B91") (pinfunction "Opto_Input_Com3_B91") (pintype "passive"))
    )
    (net (code "242") (name "unconnected-(U18B-Opto_Input_Com4-PadB101)") (class "Default")
      (node (ref "U18") (pin "B101") (pinfunction "Opto_Input_Com4_B101") (pintype "passive"))
    )
    (net (code "243") (name "unconnected-(U18B-Opto_Input_Com5-PadB111)") (class "Default")
      (node (ref "U18") (pin "B111") (pinfunction "Opto_Input_Com5_B111") (pintype "passive"))
    )
    (net (code "244") (name "unconnected-(U18B-PosLimt4-PadB11)") (class "Default")
      (node (ref "U18") (pin "B11") (pinfunction "PosLimt4_B11") (pintype "passive"))
    )
    (net (code "245") (name "unconnected-(U18B-Step4-PadB37)") (class "Default")
      (node (ref "U18") (pin "B37") (pinfunction "Step4_B37") (pintype "passive"))
    )
    (net (code "246") (name "unconnected-(U18B-~Home1-PadB7)") (class "Default")
      (node (ref "U18") (pin "B7") (pinfunction "~Home1_B7") (pintype "passive"))
    )
    (net (code "247") (name "unconnected-(U18B-~Home2-PadB5)") (class "Default")
      (node (ref "U18") (pin "B5") (pinfunction "~Home2_B5") (pintype "passive"))
    )
    (net (code "248") (name "unconnected-(U18B-~Home3-PadB3)") (class "Default")
      (node (ref "U18") (pin "B3") (pinfunction "~Home3_B3") (pintype "passive"))
    )
    (net (code "249") (name "unconnected-(U18B-~Home4-PadB1)") (class "Default")
      (node (ref "U18") (pin "B1") (pinfunction "~Home4_B1") (pintype "passive"))
    )
  )
)
